# Power_Supply.net
KiCad netlist of a schematic drawn in Altium Designer
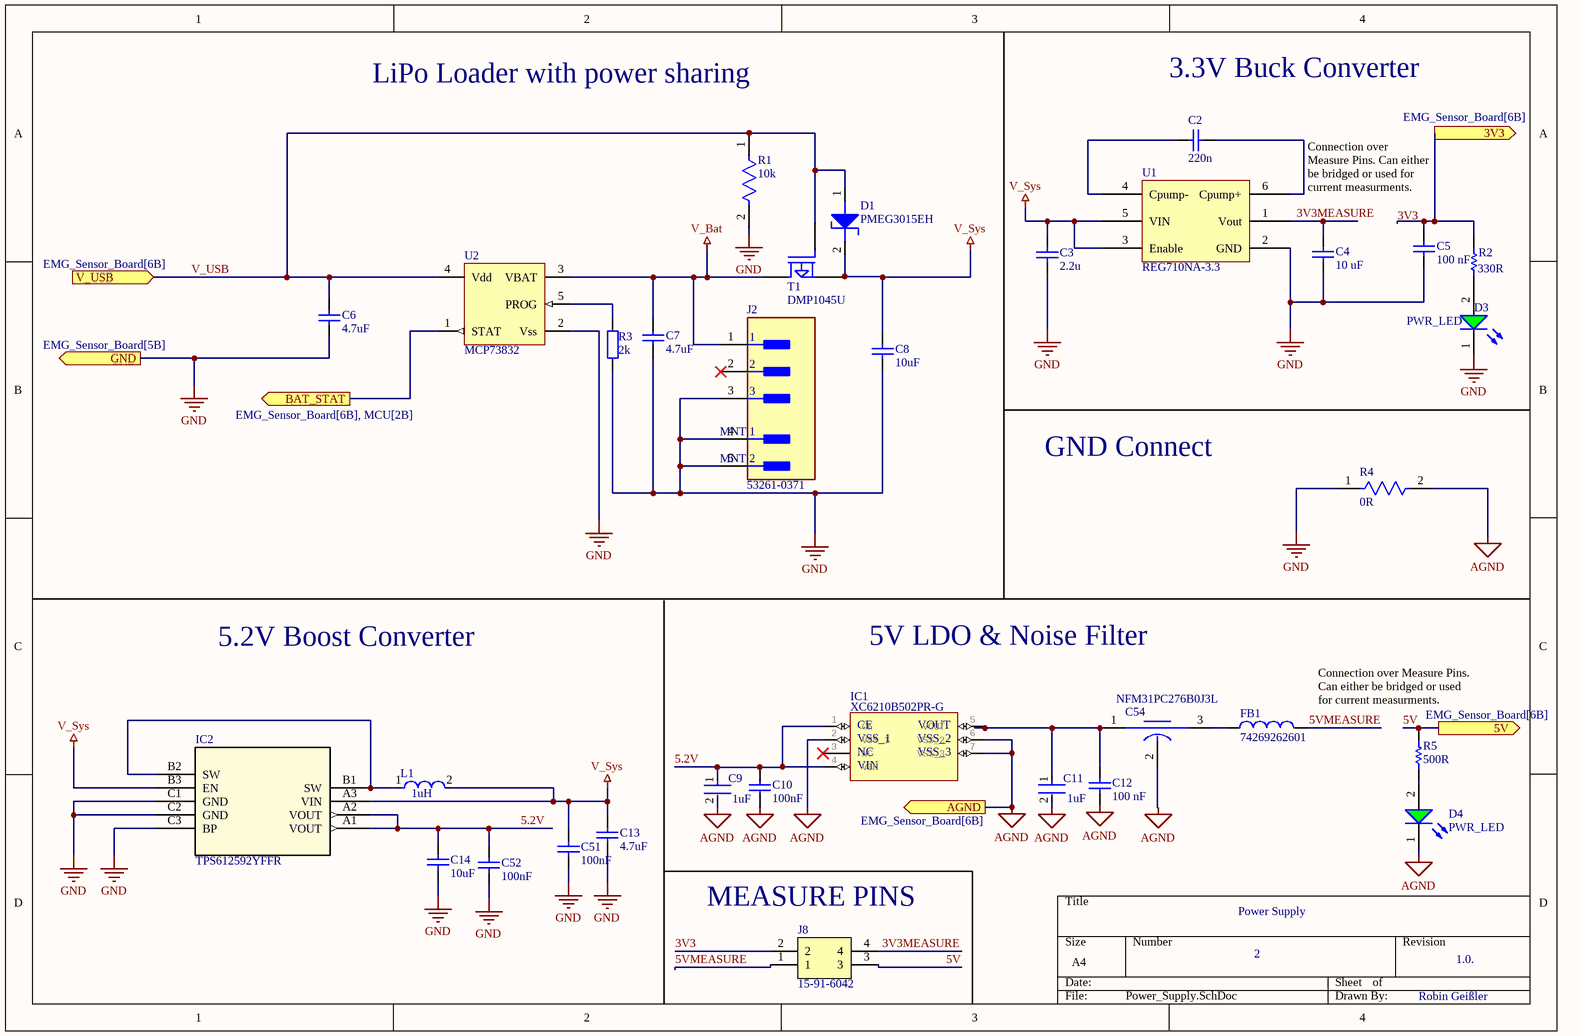
[diagram p0: Power_Supply.SchDoc]

(export (version "E")
  (design (tool "Eeschema 10.0.6"))
  (components
    (comp (ref "C2")
      (value "220n")
      (footprint "C-1608 [0603]-N")
      (description "CAP 0603 50V 0.22uF X7R 10% AEC-Q200")
      (libsource (lib "M3Infekt_V2") (part "C220n_0603_CGA3E3X7R1H224K080AB"))
    )
    (comp (ref "C3")
      (value "2.2u")
      (footprint "C-1608 [0603]-N")
      (description "CAP 0603 2.2uF 25volts X5R 10%")
      (libsource (lib "M3Infekt_V2") (part "C2u2_0603_GRM188R61E225KA12D"))
    )
    (comp (ref "C4")
      (value "10 uF")
      (footprint "C-1608 [0603]-N")
      (description "CAP CER 10UF 25V X5R 0603 10%")
      (libsource (lib "M3Infekt_V2") (part "C10u_0603_GRM188R61E106KA73J"))
    )
    (comp (ref "C5")
      (value "100 nF")
      (footprint "C-1608 [0603]-N")
      (description "Multilayer Ceramic Capacitors MLCC - SMD/SMT 16volts 0.1uF 5% X7R")
      (fields
        (field (name "MANUFACTURER") "KEMET")
        (field (name "MANUFACTURER PART NUMBER") "C0603C104J4RAC")
      )
      (libsource (lib "SERENE_Shield") (part "C100n_0603_C0603C104J4RAC"))
    )
    (comp (ref "C6")
      (value "4.7uF")
      (footprint "C-1608 [0603]-N")
      (description "CAP CER 0603 16V 4.70uF X5R 10%")
      (libsource (lib "M3Infekt_V2") (part "C4u7_0603_C1608X5R1C475K080AE"))
    )
    (comp (ref "C7")
      (value "4.7uF")
      (footprint "C-1608 [0603]-N")
      (description "CAP CER 0603 16V 4.70uF X5R 10%")
      (libsource (lib "M3Infekt_V2") (part "C4u7_0603_C1608X5R1C475K080AE"))
    )
    (comp (ref "C8")
      (value "10uF")
      (footprint "C-1608 [0603]-N")
      (description "CAP CER 10UF 25V X5R 0603 10%")
      (libsource (lib "M3Infekt_V2") (part "C10u_0603_GRM188R61E106KA73J"))
    )
    (comp (ref "C9")
      (value "1uF")
      (footprint "FP-CGA3E-0_3-0_1-IPC_B")
      (description "Cap Ceramic 1uF 35V X7R 10% Pad SMD 0603 +125°C Automotive T/R")
      (fields (field (name "TOLERANCE") "10%"))
      (libsource (lib "Altium Content Vault") (part "b4654b650e69147ec39a6b967a45e02"))
    )
    (comp (ref "C10")
      (value "100nF")
      (footprint "C-1608 [0603]-N")
      (description "Multilayer Ceramic Capacitors MLCC - SMD/SMT 16volts 0.1uF 5% X7R")
      (fields
        (field (name "MANUFACTURER") "KEMET")
        (field (name "MANUFACTURER PART NUMBER") "C0603C104J4RAC")
      )
      (libsource (lib "SERENE_Shield") (part "C100n_0603_C0603C104J4RAC"))
    )
    (comp (ref "C11")
      (value "1uF")
      (footprint "FP-CGA3E-0_3-0_1-MFG")
      (description "Cap Ceramic 1uF 35V X7R 10% Pad SMD 0603 +125°C Automotive T/R")
      (fields (field (name "TOLERANCE") "10%"))
      (libsource (lib "Altium Content Vault") (part "b4654b650e69147ec39a6b967a45e02"))
    )
    (comp (ref "C12")
      (value "100 nF")
      (footprint "C-1608 [0603]-N")
      (description "Multilayer Ceramic Capacitors MLCC - SMD/SMT 16volts 0.1uF 5% X7R")
      (fields
        (field (name "MANUFACTURER") "KEMET")
        (field (name "MANUFACTURER PART NUMBER") "C0603C104J4RAC")
      )
      (libsource (lib "SERENE_Shield") (part "C100n_0603_C0603C104J4RAC"))
    )
    (comp (ref "C13")
      (value "4.7uF")
      (footprint "C-1608 [0603]-N")
      (description "CAP CER 0603 16V 4.70uF X5R 10%")
      (libsource (lib "M3Infekt_V2") (part "C4u7_0603_C1608X5R1C475K080AE"))
    )
    (comp (ref "C14")
      (value "10uF")
      (footprint "C-1608 [0603]-N")
      (description "CAP CER 10UF 25V X5R 0603 10%")
      (libsource (lib "M3Infekt_V2") (part "C10u_0603_GRM188R61E106KA73J"))
    )
    (comp (ref "C51")
      (value "100nF")
      (footprint "C-1608 [0603]-N")
      (description "Multilayer Ceramic Capacitors MLCC - SMD/SMT 16volts 0.1uF 5% X7R")
      (fields
        (field (name "MANUFACTURER") "KEMET")
        (field (name "MANUFACTURER PART NUMBER") "C0603C104J4RAC")
      )
      (libsource (lib "SERENE_Shield") (part "C100n_0603_C0603C104J4RAC"))
    )
    (comp (ref "C52")
      (value "100nF")
      (footprint "C-1608 [0603]-N")
      (description "Multilayer Ceramic Capacitors MLCC - SMD/SMT 16volts 0.1uF 5% X7R")
      (fields
        (field (name "MANUFACTURER") "KEMET")
        (field (name "MANUFACTURER PART NUMBER") "C0603C104J4RAC")
      )
      (libsource (lib "SERENE_Shield") (part "C100n_0603_C0603C104J4RAC"))
    )
    (comp (ref "C54")
      (value "NFM31PC276B0J3L")
      (footprint "FP-NFM31-0_2-MFG")
      (fields (field (name "VOLTAGE") "6.3V") (field (name "TOLERANCE") "20%"))
      (libsource (lib "Altium Content Vault") (part "968ca41a07abfef6fd4f7114a56c54f"))
    )
    (comp (ref "D1")
      (value "PMEG3015EH")
      (footprint "SOD-123-D")
      (libsource (lib "EMG_Sensor") (part "PMEG3015EH"))
    )
    (comp (ref "D3")
      (value "PWR_LED")
      (footprint "WL-SMCW_0603_150060xx75000")
      (libsource (lib "Altium Content Vault") (part "LED_Green_2A-1K"))
    )
    (comp (ref "D4")
      (value "PWR_LED")
      (footprint "WL-SMCW_0603_150060xx75000")
      (libsource (lib "Altium Content Vault") (part "LED_Green_2A-1K"))
    )
    (comp (ref "FB1")
      (value "74269262601")
      (footprint "WE-TMSB_0603_HC")
      (description "74269262601 Ferrite Bead, Suppression, 600 Ohm, 1.5A Rohs Compliant: Yes")
      (libsource (lib "Altium Content Vault") (part "Ferrite"))
    )
    (comp (ref "IC1")
      (value "XC6210B502PR-G")
      (footprint "XC6210B502PRG")
      (description "LDO Voltage Regulators 700mA High Speed LDO Regulator   Source:  Datasheet")
      (fields (field (name "MOUSER_PART_NUMBER") "865-XC6210B502PR-G"))
      (libsource (lib "EMG_Sensor") (part "XC6210B502PR-G"))
    )
    (comp (ref "IC2")
      (value "TPS612592YFFR")
      (footprint "DSBGA09_1P206X1P306_TEX")
      (description "No Description Available")
      (fields (field (name "COPYRIGHT") "Copyright (C) 2024 Ultra Librarian. All rights reserved."))
      (libsource (lib "EMG_Sensor") (part "TPS612592YFFR"))
    )
    (comp (ref "J2")
      (value "53261-0371")
      (footprint "FP-53261-0371-MFG")
      (description "CONN HEADER SMD R/A 3POS 1.25MM")
      (fields
        (field (name "MANUFACTURER") "Molex")
        (field (name "OCTOPART") "https://octopart.com/53261-0371-molex-655314")
      )
      (libsource (lib "Altium Content Vault") (part "13850a6865a90496d8e6d51657cef87"))
    )
    (comp (ref "J8")
      (value "15-91-6042")
      (footprint "15916042")
      (fields (field (name "MOUSER PART NUMBER") "538-15-91-6042"))
      (libsource (lib "EMG_Sensor") (part "15-91-6042"))
    )
    (comp (ref "L1")
      (value "1uH")
      (footprint "FP-IHLP-1616BZ-FP_1_8545x-MFG")
      (description "Fixed Inductors Automotive High Saturation Series SMT 1uH 3.75A 37mΩ 20%")
      (fields (field (name "TOLERANCE") "20%"))
      (libsource (lib "Altium Content Vault") (part "725321dda6339637d4d059423bc1c3c"))
    )
    (comp (ref "R1")
      (value "10k")
      (footprint "FP-RC0603-0_55-IPC_C")
      (description "RES 10K OHM 1% 1/10W 0603")
      (fields (field (name "TOLERANCE") "1%"))
      (libsource (lib "Altium Content Vault") (part "1029c3af85768c4190bb7ad29bc67b5"))
    )
    (comp (ref "R2")
      (value "330R")
      (footprint "RESC1608X55X30LL15T15")
      (description "Chip Resistor, 330 Ohm, +/- 1%, 0.1 W, -55 to 155 degC, 0603 (1608 Metric), RoHS, Tape and Reel")
      (libsource (lib "Altium Content Vault") (part "RES-2"))
    )
    (comp (ref "R3")
      (value "2k")
      (footprint "C-1608 [0603]-N")
      (fields
        (field (name "MANUFACTURER") "Panasonic")
        (field (name "MANUFACTURER PART NUMBER") "ERA-3AEB202V")
        (field (name "TOLERANCE") "0.1%")
      )
      (libsource (lib "SERENE_Shield") (part "R2k_0603_ERA-3AEB202V"))
    )
    (comp (ref "R4")
      (value "0R")
      (footprint "FP-CRCW0603-e3-IPC_B")
      (description "RES Thick Film, 0Ω, 0.1W, 0603")
      (fields (field (name "TOLERANCE") "1%"))
      (libsource (lib "Altium Content Vault") (part "1029c3af85768c4190bb7ad29bc67b5"))
    )
    (comp (ref "R5")
      (value "500R")
      (footprint "RESC1608X55X30NL15T15")
      (fields (field (name "MANUFACTURER") "Panasonic") (field (name "PART NUMBER") "ERJ3EKF5100V"))
      (libsource (lib "Altium Content Vault") (part "RES"))
    )
    (comp (ref "T1")
      (value "DMP1045U")
      (footprint "SOT-23-3-PMOS")
      (description "Mouser-Nr.:621-DMP1045U-7")
      (libsource (lib "EMG_Sensor") (part "MOSFET P"))
    )
    (comp (ref "U1")
      (value "REG710NA-3.3")
      (footprint "SOT-23/6")
      (description "Schaltspannungsregler 30-mA Switched-Cap DC-DC Converter, Buck-Boost, Vout = 3.3V")
      (libsource (lib "EMG_Sensor") (part "U_SOT23-6_REG710NA-3.3"))
    )
    (comp (ref "U2")
      (value "MCP73832")
      (footprint "SOT95P280X145-5N")
      (libsource (lib "EMG_Sensor") (part "MCP73832"))
    )
  )
  (nets
    (net (code "1") (name "/3V3") (class "Default")
      (node (ref "C5") (pin "1") (pinfunction "1_1") (pintype "passive"))
      (node (ref "J8") (pin "2") (pinfunction "2_2") (pintype "passive"))
      (node (ref "R2") (pin "2") (pinfunction "2_2") (pintype "passive"))
    )
    (net (code "2") (name "/3V3MEASURE") (class "Default")
      (node (ref "C4") (pin "2") (pinfunction "2_2") (pintype "passive"))
      (node (ref "J8") (pin "4") (pinfunction "4_4") (pintype "passive"))
      (node (ref "U1") (pin "1") (pinfunction "Vout_1") (pintype "passive"))
    )
    (net (code "3") (name "/5.2V") (class "Default")
      (node (ref "C10") (pin "1") (pinfunction "1_1") (pintype "passive"))
      (node (ref "C14") (pin "2") (pinfunction "2_2") (pintype "passive"))
      (node (ref "C52") (pin "1") (pinfunction "1_1") (pintype "passive"))
      (node (ref "C9") (pin "1") (pinfunction "1_1") (pintype "passive"))
      (node (ref "IC1") (pin "1") (pinfunction "CE_1") (pintype "bidirectional"))
      (node (ref "IC1") (pin "4") (pinfunction "VIN_4") (pintype "bidirectional"))
      (node (ref "IC2") (pin "A1") (pinfunction "VOUT_A1") (pintype "output"))
      (node (ref "IC2") (pin "A2") (pinfunction "VOUT_A2") (pintype "output"))
    )
    (net (code "4") (name "/5V") (class "Default")
      (node (ref "J8") (pin "3") (pinfunction "3_3") (pintype "passive"))
      (node (ref "R5") (pin "2") (pinfunction "2_2") (pintype "passive"))
    )
    (net (code "5") (name "/5VMEASURE") (class "Default")
      (node (ref "FB1") (pin "2") (pinfunction "2_2") (pintype "passive"))
      (node (ref "J8") (pin "1") (pinfunction "1_1") (pintype "passive"))
    )
    (net (code "6") (name "/BAT_STAT") (class "Default")
      (node (ref "U2") (pin "1") (pinfunction "STAT_1") (pintype "output"))
    )
    (net (code "7") (name "/V_USB") (class "Default")
      (node (ref "C6") (pin "2") (pinfunction "2_2") (pintype "passive"))
      (node (ref "D1") (pin "1") (pinfunction "1_1") (pintype "passive"))
      (node (ref "R1") (pin "1") (pinfunction "1_1") (pintype "passive"))
      (node (ref "T1") (pin "1") (pinfunction "G_1") (pintype "passive"))
      (node (ref "U2") (pin "4") (pinfunction "Vdd_4") (pintype "power_in"))
    )
    (net (code "8") (name "AGND") (class "Default")
      (node (ref "C10") (pin "2") (pinfunction "2_2") (pintype "passive"))
      (node (ref "C11") (pin "2") (pinfunction "2_2") (pintype "passive"))
      (node (ref "C12") (pin "2") (pinfunction "2_2") (pintype "passive"))
      (node (ref "C54") (pin "2") (pinfunction "GND_2") (pintype "passive"))
      (node (ref "C9") (pin "2") (pinfunction "2_2") (pintype "passive"))
      (node (ref "D4") (pin "1") (pinfunction "K_1") (pintype "passive"))
      (node (ref "IC1") (pin "2") (pinfunction "VSS_1_2") (pintype "bidirectional"))
      (node (ref "IC1") (pin "6") (pinfunction "VSS_2_6") (pintype "bidirectional"))
      (node (ref "IC1") (pin "7") (pinfunction "VSS_3_7") (pintype "bidirectional"))
      (node (ref "R4") (pin "2") (pinfunction "2_2") (pintype "passive"))
    )
    (net (code "9") (name "GND") (class "Default")
      (node (ref "C13") (pin "1") (pinfunction "1_1") (pintype "passive"))
      (node (ref "C14") (pin "1") (pinfunction "1_1") (pintype "passive"))
      (node (ref "C3") (pin "1") (pinfunction "1_1") (pintype "passive"))
      (node (ref "C4") (pin "1") (pinfunction "1_1") (pintype "passive"))
      (node (ref "C5") (pin "2") (pinfunction "2_2") (pintype "passive"))
      (node (ref "C51") (pin "2") (pinfunction "2_2") (pintype "passive"))
      (node (ref "C52") (pin "2") (pinfunction "2_2") (pintype "passive"))
      (node (ref "C6") (pin "1") (pinfunction "1_1") (pintype "passive"))
      (node (ref "C7") (pin "1") (pinfunction "1_1") (pintype "passive"))
      (node (ref "C8") (pin "1") (pinfunction "1_1") (pintype "passive"))
      (node (ref "D3") (pin "1") (pinfunction "K_1") (pintype "passive"))
      (node (ref "IC2") (pin "C1") (pinfunction "GND_C1") (pintype "power_in"))
      (node (ref "IC2") (pin "C2") (pinfunction "GND_C2") (pintype "power_in"))
      (node (ref "IC2") (pin "C3") (pinfunction "BP_C3") (pintype "passive"))
      (node (ref "J2") (pin "3") (pinfunction "3_3") (pintype "passive"))
      (node (ref "J2") (pin "4") (pinfunction "MNT_1_4") (pintype "passive"))
      (node (ref "J2") (pin "5") (pinfunction "MNT_2_5") (pintype "passive"))
      (node (ref "R1") (pin "2") (pinfunction "2_2") (pintype "passive"))
      (node (ref "R3") (pin "1") (pinfunction "1_1") (pintype "passive"))
      (node (ref "R4") (pin "1") (pinfunction "1_1") (pintype "passive"))
      (node (ref "U1") (pin "2") (pinfunction "GND_2") (pintype "passive"))
      (node (ref "U2") (pin "2") (pinfunction "Vss_2") (pintype "power_in"))
    )
    (net (code "10") (name "Net-(C54-Input)") (class "Default")
      (node (ref "C11") (pin "1") (pinfunction "1_1") (pintype "passive"))
      (node (ref "C12") (pin "1") (pinfunction "1_1") (pintype "passive"))
      (node (ref "C54") (pin "1") (pinfunction "Input_1") (pintype "passive"))
      (node (ref "IC1") (pin "5") (pinfunction "VOUT_5") (pintype "bidirectional"))
    )
    (net (code "11") (name "Net-(C54-Output)") (class "Default")
      (node (ref "C54") (pin "3") (pinfunction "Output_3") (pintype "passive"))
      (node (ref "FB1") (pin "1") (pinfunction "1_1") (pintype "passive"))
    )
    (net (code "12") (name "Net-(D3-A)") (class "Default")
      (node (ref "D3") (pin "2") (pinfunction "A_2") (pintype "passive"))
      (node (ref "R2") (pin "1") (pinfunction "1_1") (pintype "passive"))
    )
    (net (code "13") (name "Net-(D4-A)") (class "Default")
      (node (ref "D4") (pin "2") (pinfunction "A_2") (pintype "passive"))
      (node (ref "R5") (pin "1") (pinfunction "1_1") (pintype "passive"))
    )
    (net (code "14") (name "Net-(IC2-SW-PadB1)") (class "Default")
      (node (ref "IC2") (pin "B1") (pinfunction "SW_B1") (pintype "passive"))
      (node (ref "IC2") (pin "B2") (pinfunction "SW_B2") (pintype "passive"))
      (node (ref "L1") (pin "1") (pinfunction "1_1") (pintype "passive"))
    )
    (net (code "15") (name "Net-(U1-Cpump+)") (class "Default")
      (node (ref "C2") (pin "2") (pinfunction "2_2") (pintype "passive"))
      (node (ref "U1") (pin "6") (pinfunction "Cpump+_6") (pintype "passive"))
    )
    (net (code "16") (name "Net-(U1-Cpump-)") (class "Default")
      (node (ref "C2") (pin "1") (pinfunction "1_1") (pintype "passive"))
      (node (ref "U1") (pin "4") (pinfunction "Cpump-_4") (pintype "passive"))
    )
    (net (code "17") (name "Net-(U2-PROG)") (class "Default")
      (node (ref "R3") (pin "2") (pinfunction "2_2") (pintype "passive"))
      (node (ref "U2") (pin "5") (pinfunction "PROG_5") (pintype "input"))
    )
    (net (code "18") (name "V_Bat") (class "Default")
      (node (ref "C7") (pin "2") (pinfunction "2_2") (pintype "passive"))
      (node (ref "J2") (pin "1") (pinfunction "1_1") (pintype "passive"))
      (node (ref "T1") (pin "2") (pinfunction "D_2") (pintype "passive"))
      (node (ref "U2") (pin "3") (pinfunction "VBAT_3") (pintype "power_in"))
    )
    (net (code "19") (name "V_Sys") (class "Default")
      (node (ref "C13") (pin "2") (pinfunction "2_2") (pintype "passive"))
      (node (ref "C3") (pin "2") (pinfunction "2_2") (pintype "passive"))
      (node (ref "C51") (pin "1") (pinfunction "1_1") (pintype "passive"))
      (node (ref "C8") (pin "2") (pinfunction "2_2") (pintype "passive"))
      (node (ref "D1") (pin "2") (pinfunction "2_2") (pintype "passive"))
      (node (ref "IC2") (pin "A3") (pinfunction "VIN_A3") (pintype "passive"))
      (node (ref "IC2") (pin "B3") (pinfunction "EN_B3") (pintype "passive"))
      (node (ref "L1") (pin "2") (pinfunction "2_2") (pintype "passive"))
      (node (ref "T1") (pin "3") (pinfunction "S_3") (pintype "passive"))
      (node (ref "U1") (pin "3") (pinfunction "Enable_3") (pintype "passive"))
      (node (ref "U1") (pin "5") (pinfunction "VIN_5") (pintype "passive"))
    )
    (net (code "20") (name "unconnected-(IC1-NC-Pad3)") (class "Default")
      (node (ref "IC1") (pin "3") (pinfunction "NC_3") (pintype "passive+no_connect"))
    )
    (net (code "21") (name "unconnected-(J2-Pad2)") (class "Default")
      (node (ref "J2") (pin "2") (pinfunction "2_2") (pintype "passive+no_connect"))
    )
  )
)
